# screen.net
KiCad netlist of a schematic drawn in EAGLE
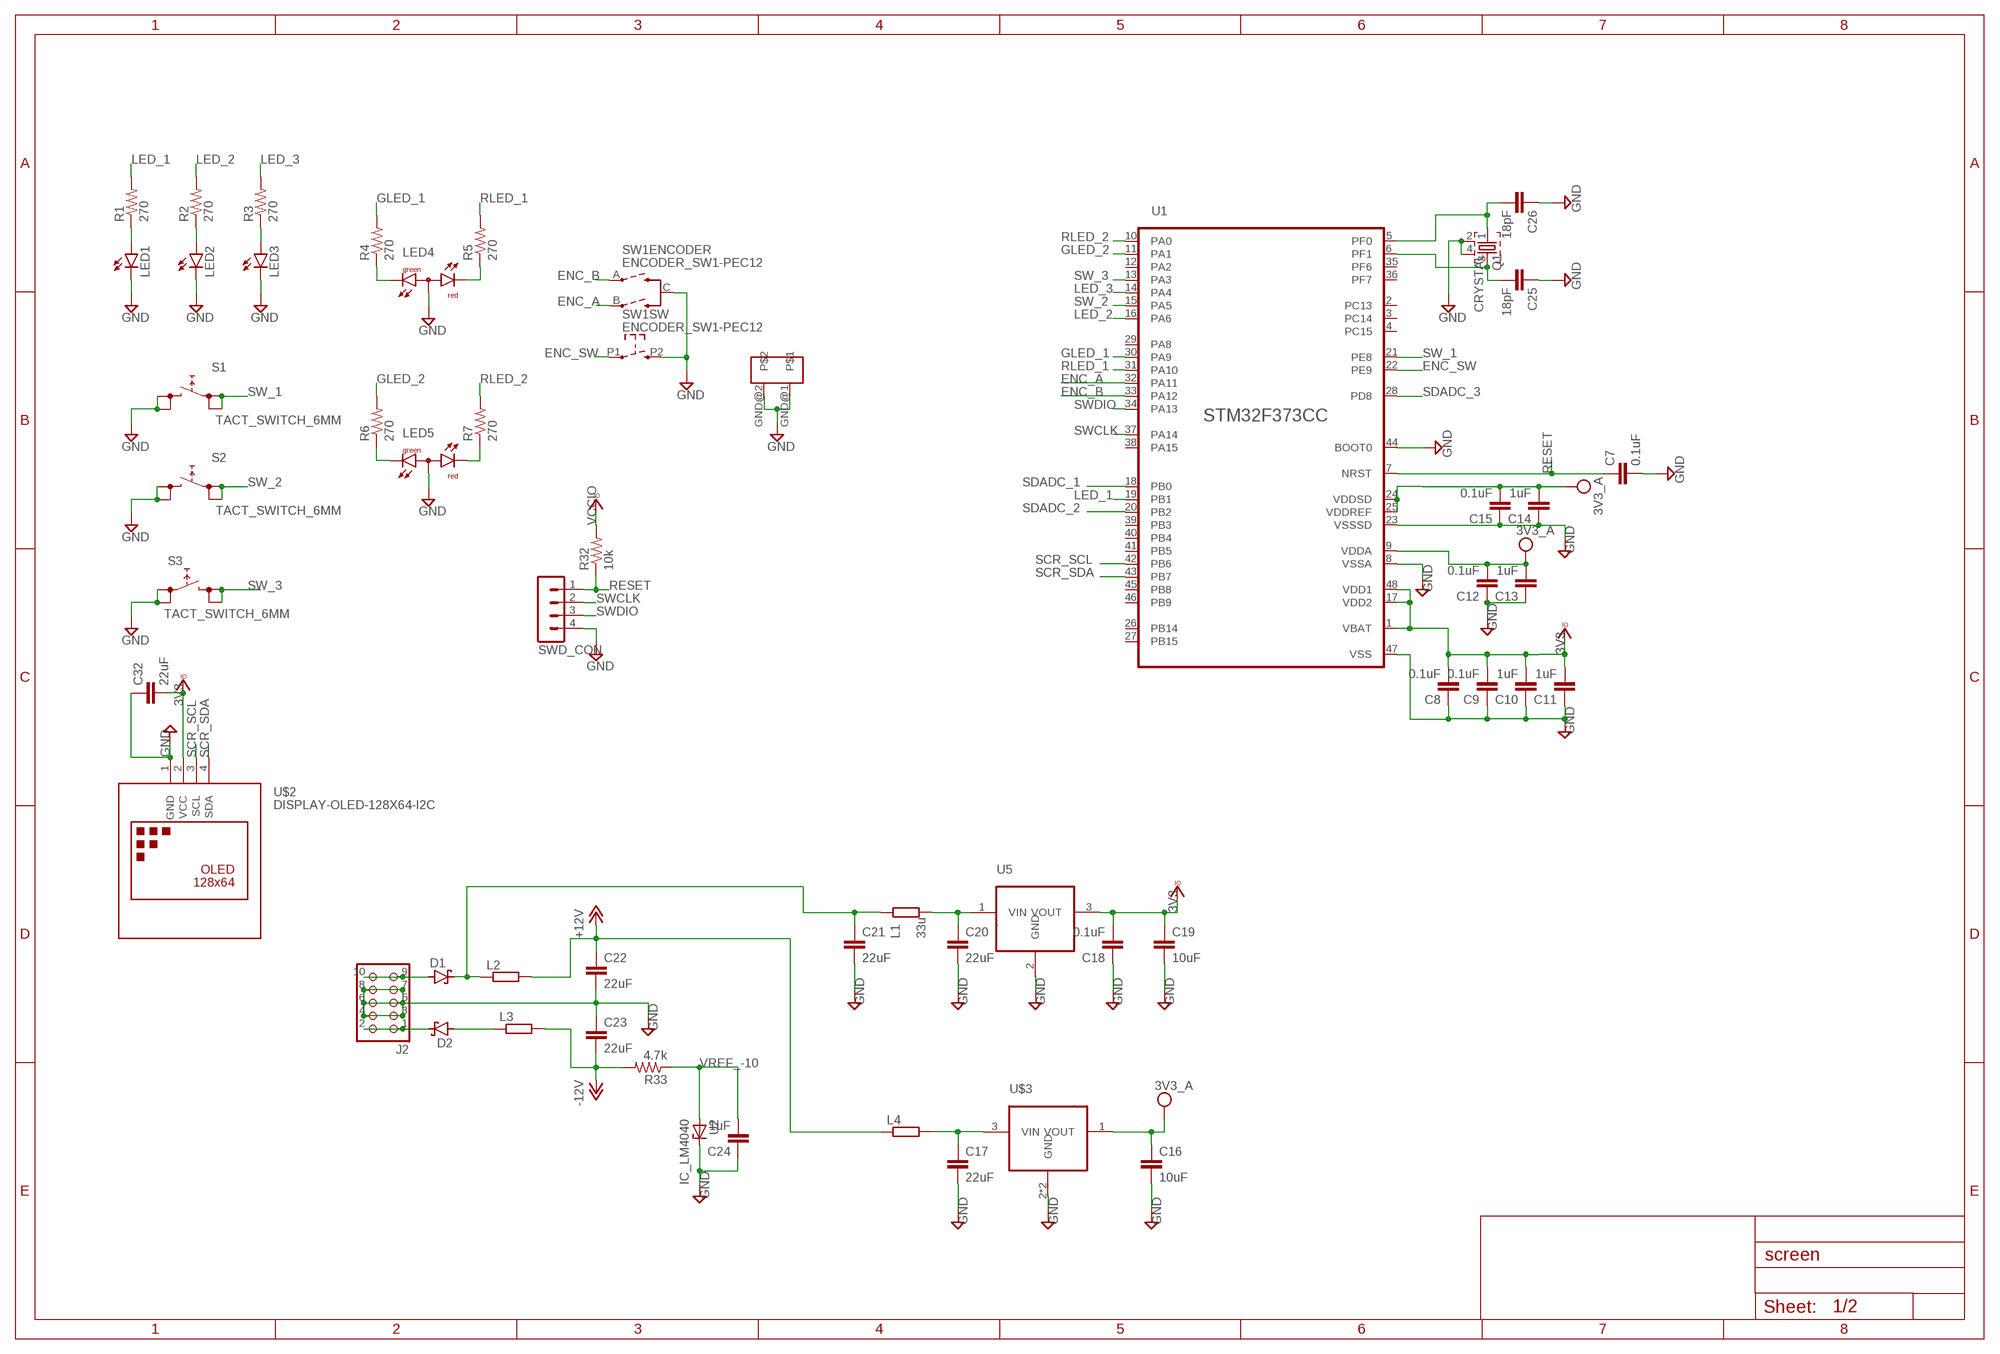
[diagram p0: schematic, sheet 1]
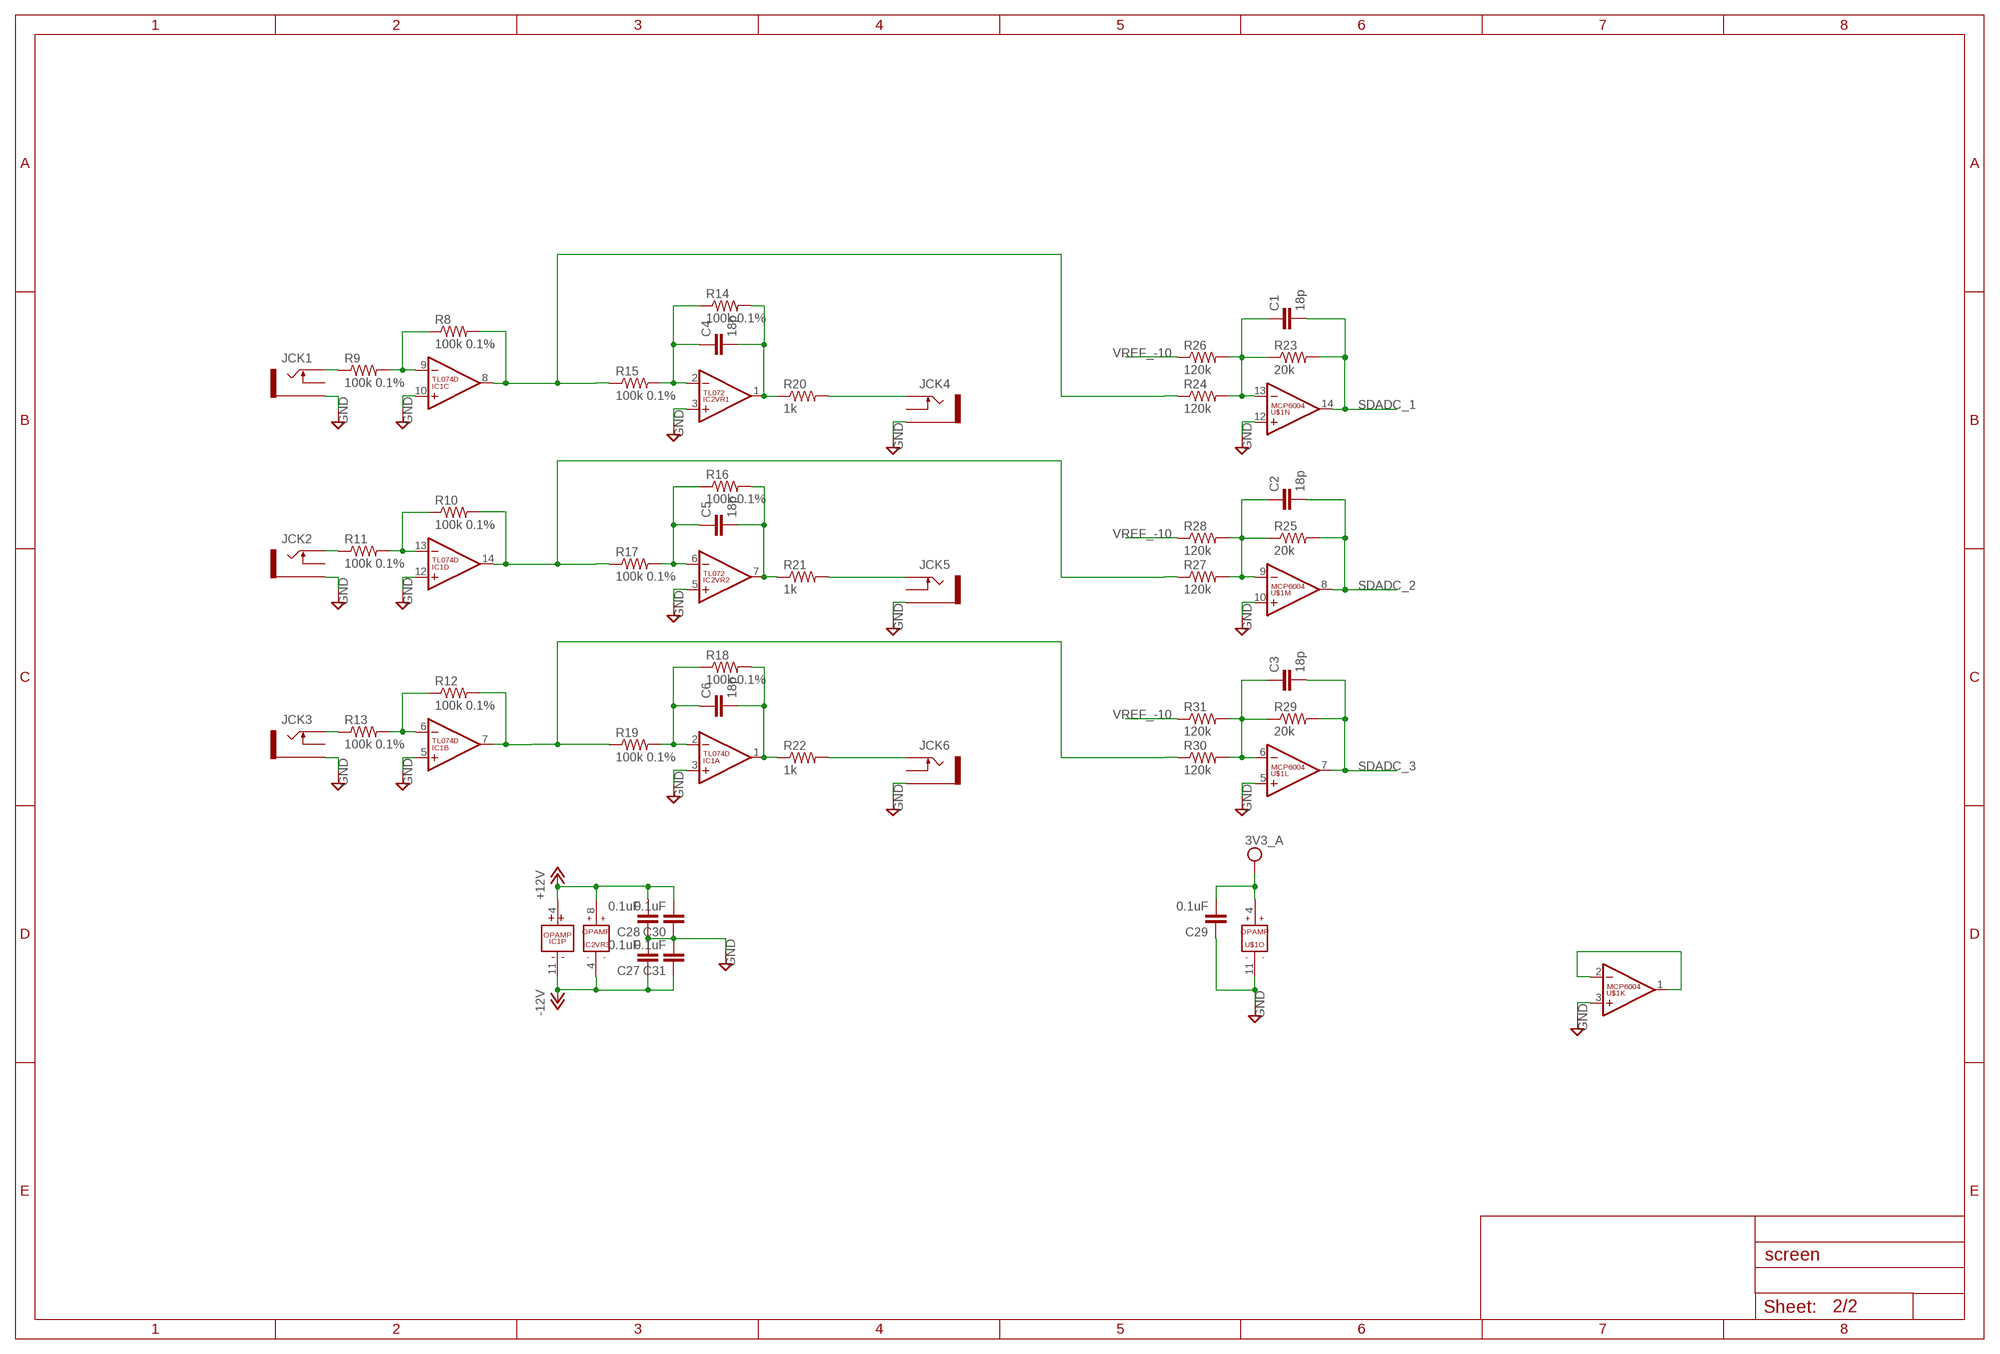
[diagram p1: schematic, sheet 2]

(export (version "E")
  (design (tool "Eeschema 10.0.6"))
  (components
    (comp (ref "C7")
      (value "0.1uF")
      (footprint "eagle-import:C0603")
      (libsource (lib "eagle-import") (part "C-EUC0603"))
    )
    (comp (ref "C8")
      (value "0.1uF")
      (footprint "eagle-import:C0603")
      (libsource (lib "eagle-import") (part "C-EUC0603"))
    )
    (comp (ref "C9")
      (value "0.1uF")
      (footprint "eagle-import:C0603")
      (libsource (lib "eagle-import") (part "C-EUC0603"))
    )
    (comp (ref "C10")
      (value "1uF")
      (footprint "eagle-import:C0603")
      (libsource (lib "eagle-import") (part "C-EUC0603"))
    )
    (comp (ref "C11")
      (value "1uF")
      (footprint "eagle-import:C0603")
      (libsource (lib "eagle-import") (part "C-EUC0603"))
    )
    (comp (ref "C12")
      (value "0.1uF")
      (footprint "eagle-import:C0603")
      (libsource (lib "eagle-import") (part "C-EUC0603"))
    )
    (comp (ref "C13")
      (value "1uF")
      (footprint "eagle-import:C0603")
      (libsource (lib "eagle-import") (part "C-EUC0603"))
    )
    (comp (ref "C14")
      (value "1uF")
      (footprint "eagle-import:C0603")
      (libsource (lib "eagle-import") (part "C-EUC0603"))
    )
    (comp (ref "C15")
      (value "0.1uF")
      (footprint "eagle-import:C0603")
      (libsource (lib "eagle-import") (part "C-EUC0603"))
    )
    (comp (ref "C16")
      (value "10uF")
      (footprint "eagle-import:C1206")
      (libsource (lib "eagle-import") (part "C-EUC1206"))
    )
    (comp (ref "C17")
      (value "22uF")
      (footprint "eagle-import:C1206")
      (libsource (lib "eagle-import") (part "C-EUC1206"))
    )
    (comp (ref "C18")
      (value "0.1uF")
      (footprint "eagle-import:C0603")
      (libsource (lib "eagle-import") (part "C-EUC0603"))
    )
    (comp (ref "C19")
      (value "10uF")
      (footprint "eagle-import:C1206")
      (libsource (lib "eagle-import") (part "C-EUC1206"))
    )
    (comp (ref "C20")
      (value "22uF")
      (footprint "eagle-import:C1206")
      (libsource (lib "eagle-import") (part "C-EUC1206"))
    )
    (comp (ref "C21")
      (value "22uF")
      (footprint "eagle-import:C1206")
      (libsource (lib "eagle-import") (part "C-EUC1206"))
    )
    (comp (ref "C22")
      (value "22uF")
      (footprint "eagle-import:C1206")
      (libsource (lib "eagle-import") (part "C-EUC1206"))
    )
    (comp (ref "C23")
      (value "22uF")
      (footprint "eagle-import:C1206")
      (libsource (lib "eagle-import") (part "C-EUC1206"))
    )
    (comp (ref "C24")
      (value "1uF")
      (footprint "eagle-import:C0603")
      (libsource (lib "eagle-import") (part "C-EUC0603"))
    )
    (comp (ref "C25")
      (value "18pF")
      (footprint "eagle-import:C0603")
      (libsource (lib "eagle-import") (part "C-EUC0603"))
    )
    (comp (ref "C26")
      (value "18pF")
      (footprint "eagle-import:C0603")
      (libsource (lib "eagle-import") (part "C-EUC0603"))
    )
    (comp (ref "C32")
      (value "22uF")
      (footprint "eagle-import:C1206")
      (libsource (lib "eagle-import") (part "C-EUC1206"))
    )
    (comp (ref "D1")
      (value "SMF5.0AT1")
      (footprint "eagle-import:SOD123FL")
      (libsource (lib "eagle-import") (part "SMF5.0AT1"))
    )
    (comp (ref "D2")
      (value "SMF5.0AT1")
      (footprint "eagle-import:SOD123FL")
      (libsource (lib "eagle-import") (part "SMF5.0AT1"))
    )
    (comp (ref "J2")
      (value "CON_HEADER_2X05-PTH+SHROUDED_A")
      (footprint "eagle-import:PINSHRD_PTH_2X05")
      (libsource (lib "eagle-import") (part "CON_HEADER_2X05-PTH+SHROUDED_A"))
    )
    (comp (ref "L1")
      (value "33u")
      (footprint "eagle-import:R0805")
      (libsource (lib "eagle-import") (part "R-EU_R0805"))
    )
    (comp (ref "L2")
      (value "R-EU_R0603")
      (footprint "eagle-import:R0603")
      (libsource (lib "eagle-import") (part "R-EU_R0603"))
    )
    (comp (ref "L3")
      (value "R-EU_R0603")
      (footprint "eagle-import:R0603")
      (libsource (lib "eagle-import") (part "R-EU_R0603"))
    )
    (comp (ref "L4")
      (value "R-EU_R0603")
      (footprint "eagle-import:R0603")
      (libsource (lib "eagle-import") (part "R-EU_R0603"))
    )
    (comp (ref "LED1")
      (value "LED3MM")
      (footprint "eagle-import:LED3MM")
      (libsource (lib "eagle-import") (part "LED3MM"))
    )
    (comp (ref "LED2")
      (value "LED3MM")
      (footprint "eagle-import:LED3MM")
      (libsource (lib "eagle-import") (part "LED3MM"))
    )
    (comp (ref "LED3")
      (value "LED3MM")
      (footprint "eagle-import:LED3MM")
      (libsource (lib "eagle-import") (part "LED3MM"))
    )
    (comp (ref "LED4")
      (value "L-115WEGW-CA")
      (footprint "eagle-import:DUOLED-A-3MM")
      (libsource (lib "eagle-import") (part "L-115WEGW-CA"))
    )
    (comp (ref "LED5")
      (value "L-115WEGW-CA")
      (footprint "eagle-import:DUOLED-A-3MM")
      (libsource (lib "eagle-import") (part "L-115WEGW-CA"))
    )
    (comp (ref "Q1")
      (value "CRYSTAL")
      (footprint "eagle-import:CTS406")
      (libsource (lib "eagle-import") (part "CRYSTAL"))
    )
    (comp (ref "R1")
      (value "270")
      (footprint "eagle-import:R0603")
      (libsource (lib "eagle-import") (part "R-US_R0603"))
    )
    (comp (ref "R2")
      (value "270")
      (footprint "eagle-import:R0603")
      (libsource (lib "eagle-import") (part "R-US_R0603"))
    )
    (comp (ref "R3")
      (value "270")
      (footprint "eagle-import:R0603")
      (libsource (lib "eagle-import") (part "R-US_R0603"))
    )
    (comp (ref "R4")
      (value "270")
      (footprint "eagle-import:R0603")
      (libsource (lib "eagle-import") (part "R-US_R0603"))
    )
    (comp (ref "R5")
      (value "270")
      (footprint "eagle-import:R0603")
      (libsource (lib "eagle-import") (part "R-US_R0603"))
    )
    (comp (ref "R6")
      (value "270")
      (footprint "eagle-import:R0603")
      (libsource (lib "eagle-import") (part "R-US_R0603"))
    )
    (comp (ref "R7")
      (value "270")
      (footprint "eagle-import:R0603")
      (libsource (lib "eagle-import") (part "R-US_R0603"))
    )
    (comp (ref "R32")
      (value "10k")
      (footprint "eagle-import:R0603")
      (libsource (lib "eagle-import") (part "R-US_R0603"))
    )
    (comp (ref "R33")
      (value "4.7k")
      (footprint "eagle-import:R0603")
      (libsource (lib "eagle-import") (part "R-US_R0603"))
    )
    (comp (ref "S1")
      (value "TACT_SWITCH_6MM")
      (footprint "eagle-import:TACT_SWITCH_6MM")
      (libsource (lib "eagle-import") (part "TACT_SWITCH_6MM"))
    )
    (comp (ref "S2")
      (value "TACT_SWITCH_6MM")
      (footprint "eagle-import:TACT_SWITCH_6MM")
      (libsource (lib "eagle-import") (part "TACT_SWITCH_6MM"))
    )
    (comp (ref "S3")
      (value "TACT_SWITCH_6MM")
      (footprint "eagle-import:TACT_SWITCH_6MM")
      (libsource (lib "eagle-import") (part "TACT_SWITCH_6MM"))
    )
    (comp (ref "SW1")
      (value "ENCODER_SW1-PEC12")
      (footprint "eagle-import:PEC12_INCREMENTAL_ENCODER")
      (libsource (lib "eagle-import") (part "ENCODER_SW1-PEC12"))
    )
    (comp (ref "SWD_CON")
      (value "MA04-1")
      (footprint "eagle-import:MA04-1")
      (libsource (lib "eagle-import") (part "MA04-1"))
    )
    (comp (ref "U$2")
      (value "DISPLAY-OLED-128X64-I2C")
      (footprint "eagle-import:DISPLAY-OLED-128X64-I2C")
      (libsource (lib "eagle-import") (part "DISPLAY-OLED-128X64-I2C"))
    )
    (comp (ref "U$3")
      (value "LD2981ABUSOT89")
      (footprint "eagle-import:SOT89")
      (libsource (lib "eagle-import") (part "LD2981ABUSOT89"))
    )
    (comp (ref "U1")
      (value "STM32F373LQFP48")
      (footprint "eagle-import:LQFP48")
      (libsource (lib "eagle-import") (part "STM32F373LQFP48"))
    )
    (comp (ref "U2")
      (value "IC_LM4040")
      (footprint "eagle-import:SOT-23")
      (libsource (lib "eagle-import") (part "IC_LM4040"))
    )
    (comp (ref "U5")
      (value "R-78E-0.5")
      (footprint "eagle-import:TO-220_RECOM")
      (libsource (lib "eagle-import") (part "R-78E-0.5"))
    )
    (comp (ref "C1")
      (value "18p")
      (footprint "eagle-import:C0603")
      (libsource (lib "eagle-import") (part "C-EUC0603"))
    )
    (comp (ref "C2")
      (value "18p")
      (footprint "eagle-import:C0603")
      (libsource (lib "eagle-import") (part "C-EUC0603"))
    )
    (comp (ref "C3")
      (value "18p")
      (footprint "eagle-import:C0603")
      (libsource (lib "eagle-import") (part "C-EUC0603"))
    )
    (comp (ref "C4")
      (value "18p")
      (footprint "eagle-import:C0603")
      (libsource (lib "eagle-import") (part "C-EUC0603"))
    )
    (comp (ref "C5")
      (value "18p")
      (footprint "eagle-import:C0603")
      (libsource (lib "eagle-import") (part "C-EUC0603"))
    )
    (comp (ref "C6")
      (value "18p")
      (footprint "eagle-import:C0603")
      (libsource (lib "eagle-import") (part "C-EUC0603"))
    )
    (comp (ref "C27")
      (value "0.1uF")
      (footprint "eagle-import:C0603")
      (libsource (lib "eagle-import") (part "C-EUC0603"))
    )
    (comp (ref "C28")
      (value "0.1uF")
      (footprint "eagle-import:C0603")
      (libsource (lib "eagle-import") (part "C-EUC0603"))
    )
    (comp (ref "C29")
      (value "0.1uF")
      (footprint "eagle-import:C0603")
      (libsource (lib "eagle-import") (part "C-EUC0603"))
    )
    (comp (ref "C30")
      (value "0.1uF")
      (footprint "eagle-import:C0603")
      (libsource (lib "eagle-import") (part "C-EUC0603"))
    )
    (comp (ref "C31")
      (value "0.1uF")
      (footprint "eagle-import:C0603")
      (libsource (lib "eagle-import") (part "C-EUC0603"))
    )
    (comp (ref "IC1")
      (value "TL074D")
      (footprint "eagle-import:SO14")
      (libsource (lib "eagle-import") (part "TL074D"))
    )
    (comp (ref "IC2")
      (value "TL072")
      (footprint "eagle-import:SO08")
      (libsource (lib "eagle-import") (part "TL072"))
    )
    (comp (ref "JCK1")
      (value "THONKICONNNEW")
      (footprint "eagle-import:WQP-PJ301M-12_JACK")
      (libsource (lib "eagle-import") (part "THONKICONNNEW"))
    )
    (comp (ref "JCK2")
      (value "THONKICONNNEW")
      (footprint "eagle-import:WQP-PJ301M-12_JACK")
      (libsource (lib "eagle-import") (part "THONKICONNNEW"))
    )
    (comp (ref "JCK3")
      (value "THONKICONNNEW")
      (footprint "eagle-import:WQP-PJ301M-12_JACK")
      (libsource (lib "eagle-import") (part "THONKICONNNEW"))
    )
    (comp (ref "JCK4")
      (value "THONKICONNNEW")
      (footprint "eagle-import:WQP-PJ301M-12_JACK")
      (libsource (lib "eagle-import") (part "THONKICONNNEW"))
    )
    (comp (ref "JCK5")
      (value "THONKICONNNEW")
      (footprint "eagle-import:WQP-PJ301M-12_JACK")
      (libsource (lib "eagle-import") (part "THONKICONNNEW"))
    )
    (comp (ref "JCK6")
      (value "THONKICONNNEW")
      (footprint "eagle-import:WQP-PJ301M-12_JACK")
      (libsource (lib "eagle-import") (part "THONKICONNNEW"))
    )
    (comp (ref "R8")
      (value "100k 0.1%")
      (footprint "eagle-import:R0603")
      (libsource (lib "eagle-import") (part "R-US_R0603"))
    )
    (comp (ref "R9")
      (value "100k 0.1%")
      (footprint "eagle-import:R0603")
      (libsource (lib "eagle-import") (part "R-US_R0603"))
    )
    (comp (ref "R10")
      (value "100k 0.1%")
      (footprint "eagle-import:R0603")
      (libsource (lib "eagle-import") (part "R-US_R0603"))
    )
    (comp (ref "R11")
      (value "100k 0.1%")
      (footprint "eagle-import:R0603")
      (libsource (lib "eagle-import") (part "R-US_R0603"))
    )
    (comp (ref "R12")
      (value "100k 0.1%")
      (footprint "eagle-import:R0603")
      (libsource (lib "eagle-import") (part "R-US_R0603"))
    )
    (comp (ref "R13")
      (value "100k 0.1%")
      (footprint "eagle-import:R0603")
      (libsource (lib "eagle-import") (part "R-US_R0603"))
    )
    (comp (ref "R14")
      (value "100k 0.1%")
      (footprint "eagle-import:R0603")
      (libsource (lib "eagle-import") (part "R-US_R0603"))
    )
    (comp (ref "R15")
      (value "100k 0.1%")
      (footprint "eagle-import:R0603")
      (libsource (lib "eagle-import") (part "R-US_R0603"))
    )
    (comp (ref "R16")
      (value "100k 0.1%")
      (footprint "eagle-import:R0603")
      (libsource (lib "eagle-import") (part "R-US_R0603"))
    )
    (comp (ref "R17")
      (value "100k 0.1%")
      (footprint "eagle-import:R0603")
      (libsource (lib "eagle-import") (part "R-US_R0603"))
    )
    (comp (ref "R18")
      (value "100k 0.1%")
      (footprint "eagle-import:R0603")
      (libsource (lib "eagle-import") (part "R-US_R0603"))
    )
    (comp (ref "R19")
      (value "100k 0.1%")
      (footprint "eagle-import:R0603")
      (libsource (lib "eagle-import") (part "R-US_R0603"))
    )
    (comp (ref "R20")
      (value "1k")
      (footprint "eagle-import:R0603")
      (libsource (lib "eagle-import") (part "R-US_R0603"))
    )
    (comp (ref "R21")
      (value "1k")
      (footprint "eagle-import:R0603")
      (libsource (lib "eagle-import") (part "R-US_R0603"))
    )
    (comp (ref "R22")
      (value "1k")
      (footprint "eagle-import:R0603")
      (libsource (lib "eagle-import") (part "R-US_R0603"))
    )
    (comp (ref "R23")
      (value "20k")
      (footprint "eagle-import:R0603")
      (libsource (lib "eagle-import") (part "R-US_R0603"))
    )
    (comp (ref "R24")
      (value "120k")
      (footprint "eagle-import:R0603")
      (libsource (lib "eagle-import") (part "R-US_R0603"))
    )
    (comp (ref "R25")
      (value "20k")
      (footprint "eagle-import:R0603")
      (libsource (lib "eagle-import") (part "R-US_R0603"))
    )
    (comp (ref "R26")
      (value "120k")
      (footprint "eagle-import:R0603")
      (libsource (lib "eagle-import") (part "R-US_R0603"))
    )
    (comp (ref "R27")
      (value "120k")
      (footprint "eagle-import:R0603")
      (libsource (lib "eagle-import") (part "R-US_R0603"))
    )
    (comp (ref "R28")
      (value "120k")
      (footprint "eagle-import:R0603")
      (libsource (lib "eagle-import") (part "R-US_R0603"))
    )
    (comp (ref "R29")
      (value "20k")
      (footprint "eagle-import:R0603")
      (libsource (lib "eagle-import") (part "R-US_R0603"))
    )
    (comp (ref "R30")
      (value "120k")
      (footprint "eagle-import:R0603")
      (libsource (lib "eagle-import") (part "R-US_R0603"))
    )
    (comp (ref "R31")
      (value "120k")
      (footprint "eagle-import:R0603")
      (libsource (lib "eagle-import") (part "R-US_R0603"))
    )
    (comp (ref "U$1")
      (value "MCP6004")
      (footprint "eagle-import:SO14")
      (libsource (lib "eagle-import") (part "MCP6004"))
    )
  )
  (nets
    (net (code "1") (name "+12V") (class "Default")
      (node (ref "C22") (pin "1") (pinfunction "1_1") (pintype "passive"))
      (node (ref "C28") (pin "2") (pinfunction "2_2") (pintype "passive"))
      (node (ref "C30") (pin "2") (pinfunction "2_2") (pintype "passive"))
      (node (ref "IC1") (pin "4") (pinfunction "V+_4") (pintype "power_in"))
      (node (ref "IC2") (pin "8") (pinfunction "V+_8") (pintype "power_in"))
      (node (ref "L2") (pin "2") (pinfunction "2_2") (pintype "passive"))
      (node (ref "L4") (pin "1") (pinfunction "1_1") (pintype "passive"))
    )
    (net (code "2") (name "-12V") (class "Default")
      (node (ref "C23") (pin "2") (pinfunction "2_2") (pintype "passive"))
      (node (ref "C27") (pin "1") (pinfunction "1_1") (pintype "passive"))
      (node (ref "C31") (pin "1") (pinfunction "1_1") (pintype "passive"))
      (node (ref "IC1") (pin "11") (pinfunction "V-_11") (pintype "power_in"))
      (node (ref "IC2") (pin "4") (pinfunction "V-_4") (pintype "power_in"))
      (node (ref "L3") (pin "2") (pinfunction "2_2") (pintype "passive"))
      (node (ref "R33") (pin "2") (pinfunction "2_2") (pintype "passive"))
    )
    (net (code "3") (name "ENC_A") (class "Default")
      (node (ref "SW1") (pin "B") (pinfunction "B_B") (pintype "passive"))
      (node (ref "U1") (pin "32") (pinfunction "PA11_32") (pintype "bidirectional"))
    )
    (net (code "4") (name "ENC_B") (class "Default")
      (node (ref "SW1") (pin "A") (pinfunction "A_A") (pintype "passive"))
      (node (ref "U1") (pin "33") (pinfunction "PA12_33") (pintype "bidirectional"))
    )
    (net (code "5") (name "ENC_SW") (class "Default")
      (node (ref "SW1") (pin "P1") (pinfunction "1_P1") (pintype "passive"))
      (node (ref "U1") (pin "22") (pinfunction "PE9_22") (pintype "bidirectional"))
    )
    (net (code "6") (name "GLED_1") (class "Default")
      (node (ref "R4") (pin "2") (pinfunction "2_2") (pintype "passive"))
      (node (ref "U1") (pin "30") (pinfunction "PA9_30") (pintype "bidirectional"))
    )
    (net (code "7") (name "GLED_2") (class "Default")
      (node (ref "R6") (pin "2") (pinfunction "2_2") (pintype "passive"))
      (node (ref "U1") (pin "11") (pinfunction "PA1_11") (pintype "bidirectional"))
    )
    (net (code "8") (name "GND") (class "Default")
      (node (ref "C10") (pin "1") (pinfunction "1_1") (pintype "passive"))
      (node (ref "C11") (pin "1") (pinfunction "1_1") (pintype "passive"))
      (node (ref "C12") (pin "1") (pinfunction "1_1") (pintype "passive"))
      (node (ref "C13") (pin "1") (pinfunction "1_1") (pintype "passive"))
      (node (ref "C14") (pin "1") (pinfunction "1_1") (pintype "passive"))
      (node (ref "C15") (pin "1") (pinfunction "1_1") (pintype "passive"))
      (node (ref "C16") (pin "2") (pinfunction "2_2") (pintype "passive"))
      (node (ref "C17") (pin "2") (pinfunction "2_2") (pintype "passive"))
      (node (ref "C18") (pin "1") (pinfunction "1_1") (pintype "passive"))
      (node (ref "C19") (pin "2") (pinfunction "2_2") (pintype "passive"))
      (node (ref "C20") (pin "2") (pinfunction "2_2") (pintype "passive"))
      (node (ref "C21") (pin "2") (pinfunction "2_2") (pintype "passive"))
      (node (ref "C22") (pin "2") (pinfunction "2_2") (pintype "passive"))
      (node (ref "C23") (pin "1") (pinfunction "1_1") (pintype "passive"))
      (node (ref "C24") (pin "1") (pinfunction "1_1") (pintype "passive"))
      (node (ref "C25") (pin "1") (pinfunction "1_1") (pintype "passive"))
      (node (ref "C26") (pin "1") (pinfunction "1_1") (pintype "passive"))
      (node (ref "C27") (pin "2") (pinfunction "2_2") (pintype "passive"))
      (node (ref "C28") (pin "1") (pinfunction "1_1") (pintype "passive"))
      (node (ref "C29") (pin "1") (pinfunction "1_1") (pintype "passive"))
      (node (ref "C30") (pin "1") (pinfunction "1_1") (pintype "passive"))
      (node (ref "C31") (pin "2") (pinfunction "2_2") (pintype "passive"))
      (node (ref "C32") (pin "1") (pinfunction "1_1") (pintype "passive"))
      (node (ref "C7") (pin "2") (pinfunction "2_2") (pintype "passive"))
      (node (ref "C8") (pin "1") (pinfunction "1_1") (pintype "passive"))
      (node (ref "C9") (pin "1") (pinfunction "1_1") (pintype "passive"))
      (node (ref "IC1") (pin "10") (pinfunction "+IN_10") (pintype "input"))
      (node (ref "IC1") (pin "12") (pinfunction "+IN_12") (pintype "input"))
      (node (ref "IC1") (pin "3") (pinfunction "+IN_3") (pintype "input"))
      (node (ref "IC1") (pin "5") (pinfunction "+IN_5") (pintype "input"))
      (node (ref "IC2") (pin "3") (pinfunction "+IN_3") (pintype "input"))
      (node (ref "IC2") (pin "5") (pinfunction "+IN_5") (pintype "input"))
      (node (ref "J2") (pin "3") (pinfunction "3_3") (pintype "passive"))
      (node (ref "J2") (pin "4") (pinfunction "4_4") (pintype "passive"))
      (node (ref "J2") (pin "5") (pinfunction "5_5") (pintype "passive"))
      (node (ref "J2") (pin "6") (pinfunction "6_6") (pintype "passive"))
      (node (ref "J2") (pin "7") (pinfunction "7_7") (pintype "passive"))
      (node (ref "J2") (pin "8") (pinfunction "8_8") (pintype "passive"))
      (node (ref "JCK1") (pin "P$3_SLEEVE") (pinfunction "SLEEVE_P$3_SLEEVE") (pintype "passive"))
      (node (ref "JCK2") (pin "P$3_SLEEVE") (pinfunction "SLEEVE_P$3_SLEEVE") (pintype "passive"))
      (node (ref "JCK3") (pin "P$3_SLEEVE") (pinfunction "SLEEVE_P$3_SLEEVE") (pintype "passive"))
      (node (ref "JCK4") (pin "P$3_SLEEVE") (pinfunction "SLEEVE_P$3_SLEEVE") (pintype "passive"))
      (node (ref "JCK5") (pin "P$3_SLEEVE") (pinfunction "SLEEVE_P$3_SLEEVE") (pintype "passive"))
      (node (ref "JCK6") (pin "P$3_SLEEVE") (pinfunction "SLEEVE_P$3_SLEEVE") (pintype "passive"))
      (node (ref "LED1") (pin "K") (pinfunction "C_K") (pintype "passive"))
      (node (ref "LED2") (pin "K") (pinfunction "C_K") (pintype "passive"))
      (node (ref "LED3") (pin "K") (pinfunction "C_K") (pintype "passive"))
      (node (ref "LED4") (pin "2") (pinfunction "A_2") (pintype "passive"))
      (node (ref "LED5") (pin "2") (pinfunction "A_2") (pintype "passive"))
      (node (ref "Q1") (pin "2") (pinfunction "2_2") (pintype "passive"))
      (node (ref "Q1") (pin "4") (pinfunction "4_4") (pintype "passive"))
      (node (ref "S1") (pin "P$3") (pinfunction "3_P$3") (pintype "bidirectional"))
      (node (ref "S1") (pin "P$4") (pinfunction "4_P$4") (pintype "bidirectional"))
      (node (ref "S2") (pin "P$3") (pinfunction "3_P$3") (pintype "bidirectional"))
      (node (ref "S2") (pin "P$4") (pinfunction "4_P$4") (pintype "bidirectional"))
      (node (ref "S3") (pin "P$1") (pinfunction "1_P$1") (pintype "bidirectional"))
      (node (ref "S3") (pin "P$2") (pinfunction "2_P$2") (pintype "bidirectional"))
      (node (ref "SW1") (pin "C") (pinfunction "C_C") (pintype "passive"))
      (node (ref "SW1") (pin "GND@1") (pinfunction "P$1_GND@1") (pintype "bidirectional"))
      (node (ref "SW1") (pin "GND@2") (pinfunction "P$2_GND@2") (pintype "bidirectional"))
      (node (ref "SW1") (pin "P2") (pinfunction "2_P2") (pintype "passive"))
      (node (ref "SWD_CON") (pin "4") (pinfunction "4_4") (pintype "passive"))
      (node (ref "U$1") (pin "10") (pinfunction "+IN_10") (pintype "input"))
      (node (ref "U$1") (pin "11") (pinfunction "V-_11") (pintype "power_in"))
      (node (ref "U$1") (pin "12") (pinfunction "+IN_12") (pintype "input"))
      (node (ref "U$1") (pin "3") (pinfunction "+IN_3") (pintype "input"))
      (node (ref "U$1") (pin "5") (pinfunction "+IN_5") (pintype "input"))
      (node (ref "U$2") (pin "1") (pinfunction "GND_1") (pintype "power_in"))
      (node (ref "U$3") (pin "2") (pinfunction "GND_2") (pintype "bidirectional"))
      (node (ref "U$3") (pin "2@1") (pinfunction "GND_2@1") (pintype "bidirectional"))
      (node (ref "U1") (pin "23") (pinfunction "VSSSD_23") (pintype "bidirectional"))
      (node (ref "U1") (pin "44") (pinfunction "BOOT0_44") (pintype "bidirectional"))
      (node (ref "U1") (pin "47") (pinfunction "VSS_47") (pintype "bidirectional"))
      (node (ref "U1") (pin "8") (pinfunction "VSSA_8") (pintype "bidirectional"))
      (node (ref "U2") (pin "1") (pinfunction "C_1") (pintype "passive"))
      (node (ref "U5") (pin "2") (pinfunction "GND_2") (pintype "bidirectional"))
    )
    (net (code "9") (name "LED_1") (class "Default")
      (node (ref "R1") (pin "2") (pinfunction "2_2") (pintype "passive"))
      (node (ref "U1") (pin "19") (pinfunction "PB1_19") (pintype "bidirectional"))
    )
    (net (code "10") (name "LED_2") (class "Default")
      (node (ref "R2") (pin "2") (pinfunction "2_2") (pintype "passive"))
      (node (ref "U1") (pin "16") (pinfunction "PA6_16") (pintype "bidirectional"))
    )
    (net (code "11") (name "LED_3") (class "Default")
      (node (ref "R3") (pin "2") (pinfunction "2_2") (pintype "passive"))
      (node (ref "U1") (pin "14") (pinfunction "PA4_14") (pintype "bidirectional"))
    )
    (net (code "12") (name "Net-(C21-Pad1)") (class "Default")
      (node (ref "C21") (pin "1") (pinfunction "1_1") (pintype "passive"))
      (node (ref "D1") (pin "C") (pinfunction "C_C") (pintype "passive"))
      (node (ref "L1") (pin "1") (pinfunction "1_1") (pintype "passive"))
      (node (ref "L2") (pin "1") (pinfunction "1_1") (pintype "passive"))
    )
    (net (code "13") (name "Net-(D1-PadA)") (class "Default")
      (node (ref "D1") (pin "A") (pinfunction "A_A") (pintype "passive"))
      (node (ref "J2") (pin "10") (pinfunction "10_10") (pintype "passive"))
      (node (ref "J2") (pin "9") (pinfunction "9_9") (pintype "passive"))
    )
    (net (code "14") (name "Net-(D2-PadA)") (class "Default")
      (node (ref "D2") (pin "A") (pinfunction "A_A") (pintype "passive"))
      (node (ref "L3") (pin "1") (pinfunction "1_1") (pintype "passive"))
    )
    (net (code "15") (name "Net-(D2-PadC)") (class "Default")
      (node (ref "D2") (pin "C") (pinfunction "C_C") (pintype "passive"))
      (node (ref "J2") (pin "1") (pinfunction "1_1") (pintype "passive"))
      (node (ref "J2") (pin "2") (pinfunction "2_2") (pintype "passive"))
    )
    (net (code "16") (name "Net-(IC1A--IN)") (class "Default")
      (node (ref "C6") (pin "1") (pinfunction "1_1") (pintype "passive"))
      (node (ref "IC1") (pin "2") (pinfunction "-IN_2") (pintype "input"))
      (node (ref "R18") (pin "1") (pinfunction "1_1") (pintype "passive"))
      (node (ref "R19") (pin "2") (pinfunction "2_2") (pintype "passive"))
    )
    (net (code "17") (name "Net-(IC1A-OUT)") (class "Default")
      (node (ref "C6") (pin "2") (pinfunction "2_2") (pintype "passive"))
      (node (ref "IC1") (pin "1") (pinfunction "OUT_1") (pintype "output"))
      (node (ref "R18") (pin "2") (pinfunction "2_2") (pintype "passive"))
      (node (ref "R22") (pin "1") (pinfunction "1_1") (pintype "passive"))
    )
    (net (code "18") (name "Net-(IC1B--IN)") (class "Default")
      (node (ref "IC1") (pin "6") (pinfunction "-IN_6") (pintype "input"))
      (node (ref "R12") (pin "1") (pinfunction "1_1") (pintype "passive"))
      (node (ref "R13") (pin "2") (pinfunction "2_2") (pintype "passive"))
    )
    (net (code "19") (name "Net-(IC1B-OUT)") (class "Default")
      (node (ref "IC1") (pin "7") (pinfunction "OUT_7") (pintype "output"))
      (node (ref "R12") (pin "2") (pinfunction "2_2") (pintype "passive"))
      (node (ref "R19") (pin "1") (pinfunction "1_1") (pintype "passive"))
      (node (ref "R30") (pin "1") (pinfunction "1_1") (pintype "passive"))
    )
    (net (code "20") (name "Net-(IC1C--IN)") (class "Default")
      (node (ref "IC1") (pin "9") (pinfunction "-IN_9") (pintype "input"))
      (node (ref "R8") (pin "1") (pinfunction "1_1") (pintype "passive"))
      (node (ref "R9") (pin "2") (pinfunction "2_2") (pintype "passive"))
    )
    (net (code "21") (name "Net-(IC1C-OUT)") (class "Default")
      (node (ref "IC1") (pin "8") (pinfunction "OUT_8") (pintype "output"))
      (node (ref "R15") (pin "1") (pinfunction "1_1") (pintype "passive"))
      (node (ref "R24") (pin "1") (pinfunction "1_1") (pintype "passive"))
      (node (ref "R8") (pin "2") (pinfunction "2_2") (pintype "passive"))
    )
    (net (code "22") (name "Net-(IC1D--IN)") (class "Default")
      (node (ref "IC1") (pin "13") (pinfunction "-IN_13") (pintype "input"))
      (node (ref "R10") (pin "1") (pinfunction "1_1") (pintype "passive"))
      (node (ref "R11") (pin "2") (pinfunction "2_2") (pintype "passive"))
    )
    (net (code "23") (name "Net-(IC1D-OUT)") (class "Default")
      (node (ref "IC1") (pin "14") (pinfunction "OUT_14") (pintype "output"))
      (node (ref "R10") (pin "2") (pinfunction "2_2") (pintype "passive"))
      (node (ref "R17") (pin "1") (pinfunction "1_1") (pintype "passive"))
      (node (ref "R27") (pin "1") (pinfunction "1_1") (pintype "passive"))
    )
    (net (code "24") (name "Net-(IC2A--IN)") (class "Default")
      (node (ref "C4") (pin "1") (pinfunction "1_1") (pintype "passive"))
      (node (ref "IC2") (pin "2") (pinfunction "-IN_2") (pintype "input"))
      (node (ref "R14") (pin "1") (pinfunction "1_1") (pintype "passive"))
      (node (ref "R15") (pin "2") (pinfunction "2_2") (pintype "passive"))
    )
    (net (code "25") (name "Net-(IC2A-OUT)") (class "Default")
      (node (ref "C4") (pin "2") (pinfunction "2_2") (pintype "passive"))
      (node (ref "IC2") (pin "1") (pinfunction "OUT_1") (pintype "output"))
      (node (ref "R14") (pin "2") (pinfunction "2_2") (pintype "passive"))
      (node (ref "R20") (pin "1") (pinfunction "1_1") (pintype "passive"))
    )
    (net (code "26") (name "Net-(IC2B--IN)") (class "Default")
      (node (ref "C5") (pin "1") (pinfunction "1_1") (pintype "passive"))
      (node (ref "IC2") (pin "6") (pinfunction "-IN_6") (pintype "input"))
      (node (ref "R16") (pin "1") (pinfunction "1_1") (pintype "passive"))
      (node (ref "R17") (pin "2") (pinfunction "2_2") (pintype "passive"))
    )
    (net (code "27") (name "Net-(IC2B-OUT)") (class "Default")
      (node (ref "C5") (pin "2") (pinfunction "2_2") (pintype "passive"))
      (node (ref "IC2") (pin "7") (pinfunction "OUT_7") (pintype "output"))
      (node (ref "R16") (pin "2") (pinfunction "2_2") (pintype "passive"))
      (node (ref "R21") (pin "1") (pinfunction "1_1") (pintype "passive"))
    )
    (net (code "28") (name "Net-(JCK1-TIP)") (class "Default")
      (node (ref "JCK1") (pin "P$1_TIP") (pinfunction "TIP_P$1_TIP") (pintype "passive"))
      (node (ref "R9") (pin "1") (pinfunction "1_1") (pintype "passive"))
    )
    (net (code "29") (name "Net-(JCK2-TIP)") (class "Default")
      (node (ref "JCK2") (pin "P$1_TIP") (pinfunction "TIP_P$1_TIP") (pintype "passive"))
      (node (ref "R11") (pin "1") (pinfunction "1_1") (pintype "passive"))
    )
    (net (code "30") (name "Net-(JCK3-TIP)") (class "Default")
      (node (ref "JCK3") (pin "P$1_TIP") (pinfunction "TIP_P$1_TIP") (pintype "passive"))
      (node (ref "R13") (pin "1") (pinfunction "1_1") (pintype "passive"))
    )
    (net (code "31") (name "Net-(JCK4-TIP)") (class "Default")
      (node (ref "JCK4") (pin "P$1_TIP") (pinfunction "TIP_P$1_TIP") (pintype "passive"))
      (node (ref "R20") (pin "2") (pinfunction "2_2") (pintype "passive"))
    )
    (net (code "32") (name "Net-(JCK5-TIP)") (class "Default")
      (node (ref "JCK5") (pin "P$1_TIP") (pinfunction "TIP_P$1_TIP") (pintype "passive"))
      (node (ref "R21") (pin "2") (pinfunction "2_2") (pintype "passive"))
    )
    (net (code "33") (name "Net-(JCK6-TIP)") (class "Default")
      (node (ref "JCK6") (pin "P$1_TIP") (pinfunction "TIP_P$1_TIP") (pintype "passive"))
      (node (ref "R22") (pin "2") (pinfunction "2_2") (pintype "passive"))
    )
    (net (code "34") (name "Net-(LED1-PadA)") (class "Default")
      (node (ref "LED1") (pin "A") (pinfunction "A_A") (pintype "passive"))
      (node (ref "R1") (pin "1") (pinfunction "1_1") (pintype "passive"))
    )
    (net (code "35") (name "Net-(LED2-PadA)") (class "Default")
      (node (ref "LED2") (pin "A") (pinfunction "A_A") (pintype "passive"))
      (node (ref "R2") (pin "1") (pinfunction "1_1") (pintype "passive"))
    )
    (net (code "36") (name "Net-(LED3-PadA)") (class "Default")
      (node (ref "LED3") (pin "A") (pinfunction "A_A") (pintype "passive"))
      (node (ref "R3") (pin "1") (pinfunction "1_1") (pintype "passive"))
    )
    (net (code "37") (name "Net-(LED4-CG)") (class "Default")
      (node (ref "LED4") (pin "1") (pinfunction "CG_1") (pintype "passive"))
      (node (ref "R4") (pin "1") (pinfunction "1_1") (pintype "passive"))
    )
    (net (code "38") (name "Net-(LED4-CR)") (class "Default")
      (node (ref "LED4") (pin "3") (pinfunction "CR_3") (pintype "passive"))
      (node (ref "R5") (pin "1") (pinfunction "1_1") (pintype "passive"))
    )
    (net (code "39") (name "Net-(LED5-CG)") (class "Default")
      (node (ref "LED5") (pin "1") (pinfunction "CG_1") (pintype "passive"))
      (node (ref "R6") (pin "1") (pinfunction "1_1") (pintype "passive"))
    )
    (net (code "40") (name "Net-(LED5-CR)") (class "Default")
      (node (ref "LED5") (pin "3") (pinfunction "CR_3") (pintype "passive"))
      (node (ref "R7") (pin "1") (pinfunction "1_1") (pintype "passive"))
    )
    (net (code "41") (name "Net-(U$1A--IN)") (class "Default")
      (node (ref "U$1") (pin "1") (pinfunction "OUT_1") (pintype "output"))
      (node (ref "U$1") (pin "2") (pinfunction "-IN_2") (pintype "input"))
    )
    (net (code "42") (name "Net-(U$1B--IN)") (class "Default")
      (node (ref "C3") (pin "1") (pinfunction "1_1") (pintype "passive"))
      (node (ref "R29") (pin "1") (pinfunction "1_1") (pintype "passive"))
      (node (ref "R30") (pin "2") (pinfunction "2_2") (pintype "passive"))
      (node (ref "R31") (pin "2") (pinfunction "2_2") (pintype "passive"))
      (node (ref "U$1") (pin "6") (pinfunction "-IN_6") (pintype "input"))
    )
    (net (code "43") (name "Net-(U$1C--IN)") (class "Default")
      (node (ref "C2") (pin "1") (pinfunction "1_1") (pintype "passive"))
      (node (ref "R25") (pin "1") (pinfunction "1_1") (pintype "passive"))
      (node (ref "R27") (pin "2") (pinfunction "2_2") (pintype "passive"))
      (node (ref "R28") (pin "2") (pinfunction "2_2") (pintype "passive"))
      (node (ref "U$1") (pin "9") (pinfunction "-IN_9") (pintype "input"))
    )
    (net (code "44") (name "Net-(U$1D--IN)") (class "Default")
      (node (ref "C1") (pin "1") (pinfunction "1_1") (pintype "passive"))
      (node (ref "R23") (pin "1") (pinfunction "1_1") (pintype "passive"))
      (node (ref "R24") (pin "2") (pinfunction "2_2") (pintype "passive"))
      (node (ref "R26") (pin "2") (pinfunction "2_2") (pintype "passive"))
      (node (ref "U$1") (pin "13") (pinfunction "-IN_13") (pintype "input"))
    )
    (net (code "45") (name "Net-(U$3-VIN)") (class "Default")
      (node (ref "C17") (pin "1") (pinfunction "1_1") (pintype "passive"))
      (node (ref "L4") (pin "2") (pinfunction "2_2") (pintype "passive"))
      (node (ref "U$3") (pin "3") (pinfunction "VIN_3") (pintype "bidirectional"))
    )
    (net (code "46") (name "Net-(U1-PF0)") (class "Default")
      (node (ref "C26") (pin "2") (pinfunction "2_2") (pintype "passive"))
      (node (ref "Q1") (pin "1") (pinfunction "1_1") (pintype "passive"))
      (node (ref "U1") (pin "5") (pinfunction "PF0_5") (pintype "bidirectional"))
    )
    (net (code "47") (name "Net-(U1-PF1)") (class "Default")
      (node (ref "C25") (pin "2") (pinfunction "2_2") (pintype "passive"))
      (node (ref "Q1") (pin "3") (pinfunction "3_3") (pintype "passive"))
      (node (ref "U1") (pin "6") (pinfunction "PF1_6") (pintype "bidirectional"))
    )
    (net (code "48") (name "Net-(U5-VIN)") (class "Default")
      (node (ref "C20") (pin "1") (pinfunction "1_1") (pintype "passive"))
      (node (ref "L1") (pin "2") (pinfunction "2_2") (pintype "passive"))
      (node (ref "U5") (pin "1") (pinfunction "VIN_1") (pintype "bidirectional"))
    )
    (net (code "49") (name "RESET") (class "Default")
      (node (ref "C7") (pin "1") (pinfunction "1_1") (pintype "passive"))
      (node (ref "R32") (pin "1") (pinfunction "1_1") (pintype "passive"))
      (node (ref "SWD_CON") (pin "1") (pinfunction "1_1") (pintype "passive"))
      (node (ref "U1") (pin "7") (pinfunction "NRST_7") (pintype "bidirectional"))
    )
    (net (code "50") (name "RLED_1") (class "Default")
      (node (ref "R5") (pin "2") (pinfunction "2_2") (pintype "passive"))
      (node (ref "U1") (pin "31") (pinfunction "PA10_31") (pintype "bidirectional"))
    )
    (net (code "51") (name "RLED_2") (class "Default")
      (node (ref "R7") (pin "2") (pinfunction "2_2") (pintype "passive"))
      (node (ref "U1") (pin "10") (pinfunction "PA0_10") (pintype "bidirectional"))
    )
    (net (code "52") (name "SCR_SCL") (class "Default")
      (node (ref "U$2") (pin "3") (pinfunction "SCL_3") (pintype "bidirectional"))
      (node (ref "U1") (pin "42") (pinfunction "PB6_42") (pintype "bidirectional"))
    )
    (net (code "53") (name "SCR_SDA") (class "Default")
      (node (ref "U$2") (pin "4") (pinfunction "SDA_4") (pintype "bidirectional"))
      (node (ref "U1") (pin "43") (pinfunction "PB7_43") (pintype "bidirectional"))
    )
    (net (code "54") (name "SDADC_1") (class "Default")
      (node (ref "C1") (pin "2") (pinfunction "2_2") (pintype "passive"))
      (node (ref "R23") (pin "2") (pinfunction "2_2") (pintype "passive"))
      (node (ref "U$1") (pin "14") (pinfunction "OUT_14") (pintype "output"))
      (node (ref "U1") (pin "18") (pinfunction "PB0_18") (pintype "bidirectional"))
    )
    (net (code "55") (name "SDADC_2") (class "Default")
      (node (ref "C2") (pin "2") (pinfunction "2_2") (pintype "passive"))
      (node (ref "R25") (pin "2") (pinfunction "2_2") (pintype "passive"))
      (node (ref "U$1") (pin "8") (pinfunction "OUT_8") (pintype "output"))
      (node (ref "U1") (pin "20") (pinfunction "PB2_20") (pintype "bidirectional"))
    )
    (net (code "56") (name "SDADC_3") (class "Default")
      (node (ref "C3") (pin "2") (pinfunction "2_2") (pintype "passive"))
      (node (ref "R29") (pin "2") (pinfunction "2_2") (pintype "passive"))
      (node (ref "U$1") (pin "7") (pinfunction "OUT_7") (pintype "output"))
      (node (ref "U1") (pin "28") (pinfunction "PD8_28") (pintype "bidirectional"))
    )
    (net (code "57") (name "SWCLK") (class "Default")
      (node (ref "SWD_CON") (pin "2") (pinfunction "2_2") (pintype "passive"))
      (node (ref "U1") (pin "37") (pinfunction "PA14_37") (pintype "bidirectional"))
    )
    (net (code "58") (name "SWDIO") (class "Default")
      (node (ref "SWD_CON") (pin "3") (pinfunction "3_3") (pintype "passive"))
      (node (ref "U1") (pin "34") (pinfunction "PA13_34") (pintype "bidirectional"))
    )
    (net (code "59") (name "SW_1") (class "Default")
      (node (ref "S1") (pin "P$1") (pinfunction "1_P$1") (pintype "bidirectional"))
      (node (ref "S1") (pin "P$2") (pinfunction "2_P$2") (pintype "bidirectional"))
      (node (ref "U1") (pin "21") (pinfunction "PE8_21") (pintype "bidirectional"))
    )
    (net (code "60") (name "SW_2") (class "Default")
      (node (ref "S2") (pin "P$1") (pinfunction "1_P$1") (pintype "bidirectional"))
      (node (ref "S2") (pin "P$2") (pinfunction "2_P$2") (pintype "bidirectional"))
      (node (ref "U1") (pin "15") (pinfunction "PA5_15") (pintype "bidirectional"))
    )
    (net (code "61") (name "SW_3") (class "Default")
      (node (ref "S3") (pin "P$3") (pinfunction "3_P$3") (pintype "bidirectional"))
      (node (ref "S3") (pin "P$4") (pinfunction "4_P$4") (pintype "bidirectional"))
      (node (ref "U1") (pin "13") (pinfunction "PA3_13") (pintype "bidirectional"))
    )
    (net (code "62") (name "VCC") (class "Default")
      (node (ref "C12") (pin "2") (pinfunction "2_2") (pintype "passive"))
      (node (ref "C13") (pin "2") (pinfunction "2_2") (pintype "passive"))
      (node (ref "C14") (pin "2") (pinfunction "2_2") (pintype "passive"))
      (node (ref "C15") (pin "2") (pinfunction "2_2") (pintype "passive"))
      (node (ref "C16") (pin "1") (pinfunction "1_1") (pintype "passive"))
      (node (ref "C29") (pin "2") (pinfunction "2_2") (pintype "passive"))
      (node (ref "U$1") (pin "4") (pinfunction "V+_4") (pintype "power_in"))
      (node (ref "U$3") (pin "1") (pinfunction "VOUT_1") (pintype "bidirectional"))
      (node (ref "U1") (pin "24") (pinfunction "VDDSD_24") (pintype "bidirectional"))
      (node (ref "U1") (pin "25") (pinfunction "VDDREF_25") (pintype "bidirectional"))
      (node (ref "U1") (pin "9") (pinfunction "VDDA_9") (pintype "bidirectional"))
    )
    (net (code "63") (name "VCCIO") (class "Default")
      (node (ref "C10") (pin "2") (pinfunction "2_2") (pintype "passive"))
      (node (ref "C11") (pin "2") (pinfunction "2_2") (pintype "passive"))
      (node (ref "C18") (pin "2") (pinfunction "2_2") (pintype "passive"))
      (node (ref "C19") (pin "1") (pinfunction "1_1") (pintype "passive"))
      (node (ref "C32") (pin "2") (pinfunction "2_2") (pintype "passive"))
      (node (ref "C8") (pin "2") (pinfunction "2_2") (pintype "passive"))
      (node (ref "C9") (pin "2") (pinfunction "2_2") (pintype "passive"))
      (node (ref "R32") (pin "2") (pinfunction "2_2") (pintype "passive"))
      (node (ref "U$2") (pin "2") (pinfunction "VCC_2") (pintype "power_in"))
      (node (ref "U1") (pin "1") (pinfunction "VBAT_1") (pintype "bidirectional"))
      (node (ref "U1") (pin "17") (pinfunction "VDD2_17") (pintype "bidirectional"))
      (node (ref "U1") (pin "48") (pinfunction "VDD1_48") (pintype "bidirectional"))
      (node (ref "U5") (pin "3") (pinfunction "VOUT_3") (pintype "bidirectional"))
    )
    (net (code "64") (name "VREF_-10") (class "Default")
      (node (ref "C24") (pin "2") (pinfunction "2_2") (pintype "passive"))
      (node (ref "R26") (pin "1") (pinfunction "1_1") (pintype "passive"))
      (node (ref "R28") (pin "1") (pinfunction "1_1") (pintype "passive"))
      (node (ref "R31") (pin "1") (pinfunction "1_1") (pintype "passive"))
      (node (ref "R33") (pin "1") (pinfunction "1_1") (pintype "passive"))
      (node (ref "U2") (pin "2") (pinfunction "A_2") (pintype "passive"))
      (node (ref "U2") (pin "3") (pinfunction "A_3") (pintype "passive"))
    )
    (net (code "65") (name "unconnected-(JCK1-SWITCH-PadP$2_SWITCH)") (class "Default")
      (node (ref "JCK1") (pin "P$2_SWITCH") (pinfunction "SWITCH_P$2_SWITCH") (pintype "passive"))
    )
    (net (code "66") (name "unconnected-(JCK2-SWITCH-PadP$2_SWITCH)") (class "Default")
      (node (ref "JCK2") (pin "P$2_SWITCH") (pinfunction "SWITCH_P$2_SWITCH") (pintype "passive"))
    )
    (net (code "67") (name "unconnected-(JCK3-SWITCH-PadP$2_SWITCH)") (class "Default")
      (node (ref "JCK3") (pin "P$2_SWITCH") (pinfunction "SWITCH_P$2_SWITCH") (pintype "passive"))
    )
    (net (code "68") (name "unconnected-(JCK4-SWITCH-PadP$2_SWITCH)") (class "Default")
      (node (ref "JCK4") (pin "P$2_SWITCH") (pinfunction "SWITCH_P$2_SWITCH") (pintype "passive"))
    )
    (net (code "69") (name "unconnected-(JCK5-SWITCH-PadP$2_SWITCH)") (class "Default")
      (node (ref "JCK5") (pin "P$2_SWITCH") (pinfunction "SWITCH_P$2_SWITCH") (pintype "passive"))
    )
    (net (code "70") (name "unconnected-(JCK6-SWITCH-PadP$2_SWITCH)") (class "Default")
      (node (ref "JCK6") (pin "P$2_SWITCH") (pinfunction "SWITCH_P$2_SWITCH") (pintype "passive"))
    )
    (net (code "71") (name "unconnected-(U1-PA2-Pad12)") (class "Default")
      (node (ref "U1") (pin "12") (pinfunction "PA2_12") (pintype "bidirectional"))
    )
    (net (code "72") (name "unconnected-(U1-PA8-Pad29)") (class "Default")
      (node (ref "U1") (pin "29") (pinfunction "PA8_29") (pintype "bidirectional"))
    )
    (net (code "73") (name "unconnected-(U1-PA15-Pad38)") (class "Default")
      (node (ref "U1") (pin "38") (pinfunction "PA15_38") (pintype "bidirectional"))
    )
    (net (code "74") (name "unconnected-(U1-PB3-Pad39)") (class "Default")
      (node (ref "U1") (pin "39") (pinfunction "PB3_39") (pintype "bidirectional"))
    )
    (net (code "75") (name "unconnected-(U1-PB4-Pad40)") (class "Default")
      (node (ref "U1") (pin "40") (pinfunction "PB4_40") (pintype "bidirectional"))
    )
    (net (code "76") (name "unconnected-(U1-PB5-Pad41)") (class "Default")
      (node (ref "U1") (pin "41") (pinfunction "PB5_41") (pintype "bidirectional"))
    )
    (net (code "77") (name "unconnected-(U1-PB8-Pad45)") (class "Default")
      (node (ref "U1") (pin "45") (pinfunction "PB8_45") (pintype "bidirectional"))
    )
    (net (code "78") (name "unconnected-(U1-PB9-Pad46)") (class "Default")
      (node (ref "U1") (pin "46") (pinfunction "PB9_46") (pintype "bidirectional"))
    )
    (net (code "79") (name "unconnected-(U1-PB14-Pad26)") (class "Default")
      (node (ref "U1") (pin "26") (pinfunction "PB14_26") (pintype "bidirectional"))
    )
    (net (code "80") (name "unconnected-(U1-PB15-Pad27)") (class "Default")
      (node (ref "U1") (pin "27") (pinfunction "PB15_27") (pintype "bidirectional"))
    )
    (net (code "81") (name "unconnected-(U1-PC13-Pad2)") (class "Default")
      (node (ref "U1") (pin "2") (pinfunction "PC13_2") (pintype "bidirectional"))
    )
    (net (code "82") (name "unconnected-(U1-PC14-Pad3)") (class "Default")
      (node (ref "U1") (pin "3") (pinfunction "PC14_3") (pintype "bidirectional"))
    )
    (net (code "83") (name "unconnected-(U1-PC15-Pad4)") (class "Default")
      (node (ref "U1") (pin "4") (pinfunction "PC15_4") (pintype "bidirectional"))
    )
    (net (code "84") (name "unconnected-(U1-PF6-Pad35)") (class "Default")
      (node (ref "U1") (pin "35") (pinfunction "PF6_35") (pintype "bidirectional"))
    )
    (net (code "85") (name "unconnected-(U1-PF7-Pad36)") (class "Default")
      (node (ref "U1") (pin "36") (pinfunction "PF7_36") (pintype "bidirectional"))
    )
  )
)
